# Meios_pagamento.net
KiCad netlist of a schematic drawn in Altium Designer
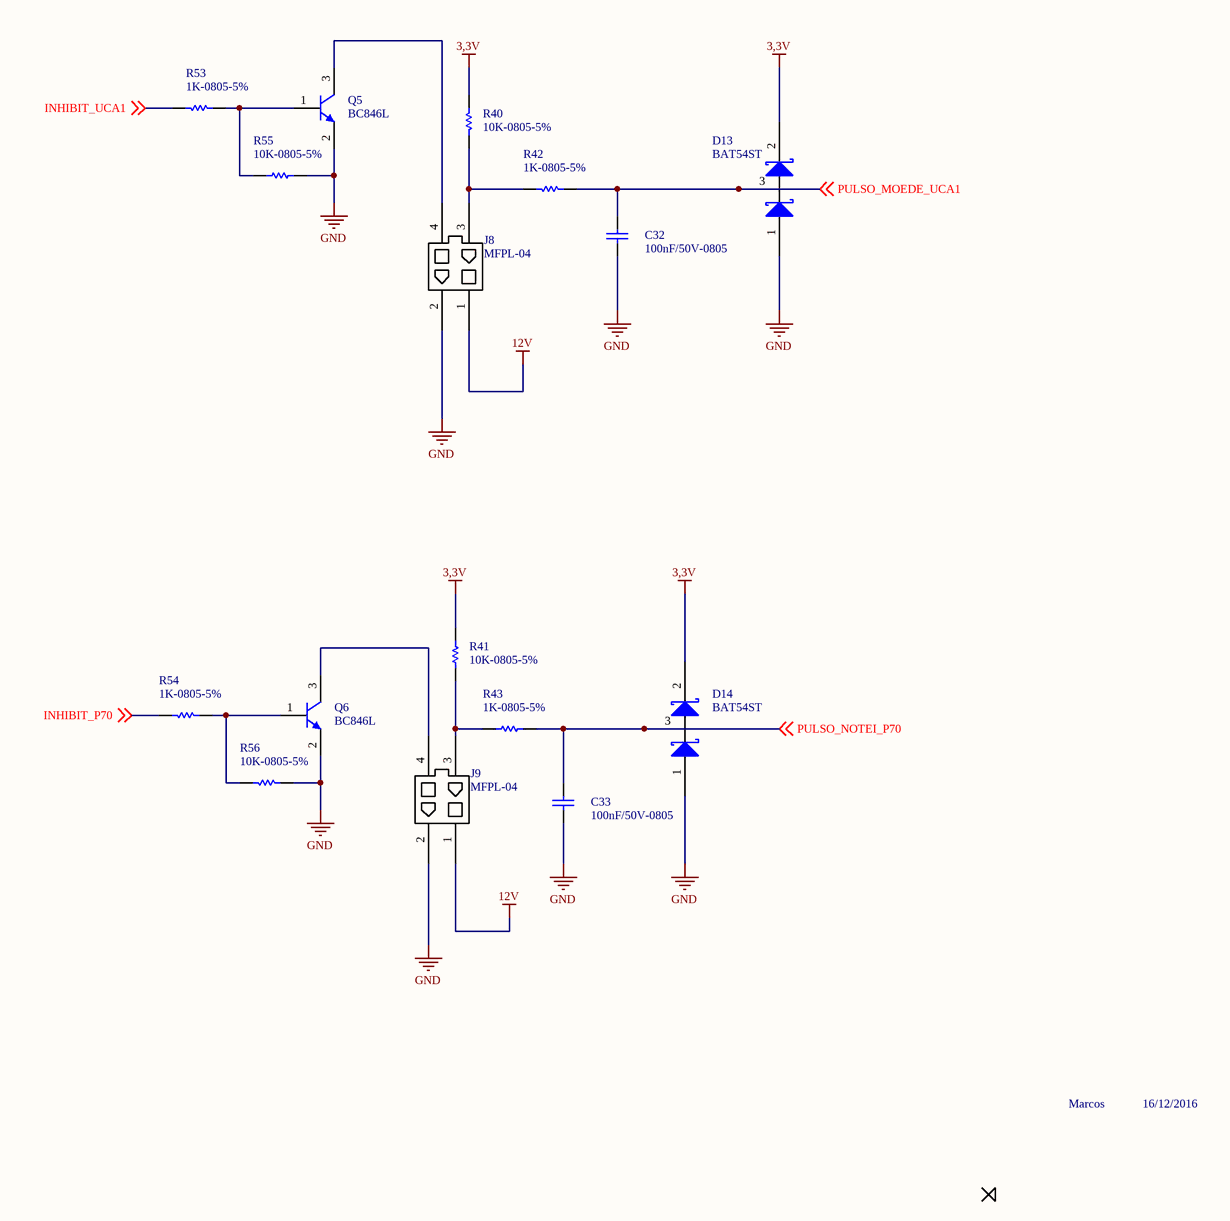
[diagram p0: Meios_pagamento.SchDoc]

(export (version "E")
  (design (tool "Eeschema 10.0.6"))
  (components
    (comp (ref "C32")
      (value "100nF/50V-0805")
      (footprint "0805-REVISADO ONDA")
      (libsource (lib "AquinoLib") (part "100nF/50-0805-NPO"))
    )
    (comp (ref "C33")
      (value "100nF/50V-0805")
      (footprint "0805-REVISADO ONDA")
      (libsource (lib "AquinoLib") (part "100nF/50-0805-NPO"))
    )
    (comp (ref "D13")
      (value "BAT54ST")
      (footprint "SOT23 - REVISADO ONDA")
      (libsource (lib "AquinoLib") (part "BAT54ST"))
    )
    (comp (ref "D14")
      (value "BAT54ST")
      (footprint "SOT23 - REVISADO ONDA")
      (libsource (lib "AquinoLib") (part "BAT54ST"))
    )
    (comp (ref "J8") (value "MFPL-04") (libsource (lib "AquinoLib") (part "MFPL-04")))
    (comp (ref "J9") (value "MFPL-04") (libsource (lib "AquinoLib") (part "MFPL-04")))
    (comp (ref "Q5")
      (value "BC846L")
      (footprint "SOT23 - REVISADO ONDA")
      (libsource (lib "AquinoLib") (part "BC846"))
    )
    (comp (ref "Q6")
      (value "BC846L")
      (footprint "SOT23 - REVISADO ONDA")
      (libsource (lib "AquinoLib") (part "BC846"))
    )
    (comp (ref "R40")
      (value "10K-0805-5%")
      (footprint "0805-REVISADO ONDA")
      (libsource (lib "AquinoLib") (part "10K-0805-5%"))
    )
    (comp (ref "R41")
      (value "10K-0805-5%")
      (footprint "0805-REVISADO ONDA")
      (libsource (lib "AquinoLib") (part "10K-0805-5%"))
    )
    (comp (ref "R42")
      (value "1K-0805-5%")
      (footprint "0805-REVISADO ONDA")
      (libsource (lib "AquinoLib") (part "1K-0805-5%"))
    )
    (comp (ref "R43")
      (value "1K-0805-5%")
      (footprint "0805-REVISADO ONDA")
      (libsource (lib "AquinoLib") (part "1K-0805-5%"))
    )
    (comp (ref "R53")
      (value "1K-0805-5%")
      (footprint "0805-REVISADO ONDA")
      (libsource (lib "AquinoLib") (part "1K-0805-5%"))
    )
    (comp (ref "R54")
      (value "1K-0805-5%")
      (footprint "0805-REVISADO ONDA")
      (libsource (lib "AquinoLib") (part "1K-0805-5%"))
    )
    (comp (ref "R55")
      (value "10K-0805-5%")
      (footprint "0805-REVISADO ONDA")
      (libsource (lib "AquinoLib") (part "10K-0805-5%"))
    )
    (comp (ref "R56")
      (value "10K-0805-5%")
      (footprint "0805-REVISADO ONDA")
      (libsource (lib "AquinoLib") (part "10K-0805-5%"))
    )
  )
  (nets
    (net (code "1") (name "3,3V") (class "Default")
      (node (ref "D13") (pin "2") (pinfunction "2_2") (pintype "passive"))
      (node (ref "D14") (pin "2") (pinfunction "2_2") (pintype "passive"))
      (node (ref "R40") (pin "2") (pinfunction "2_2") (pintype "passive"))
      (node (ref "R41") (pin "2") (pinfunction "2_2") (pintype "passive"))
    )
    (net (code "2") (name "12V") (class "Default")
      (node (ref "J8") (pin "1") (pinfunction "1_1") (pintype "passive"))
      (node (ref "J9") (pin "1") (pinfunction "1_1") (pintype "passive"))
    )
    (net (code "3") (name "GND") (class "Default")
      (node (ref "C32") (pin "1") (pinfunction "1_1") (pintype "passive"))
      (node (ref "C33") (pin "1") (pinfunction "1_1") (pintype "passive"))
      (node (ref "D13") (pin "1") (pinfunction "1_1") (pintype "passive"))
      (node (ref "D14") (pin "1") (pinfunction "1_1") (pintype "passive"))
      (node (ref "J8") (pin "2") (pinfunction "2_2") (pintype "passive"))
      (node (ref "J9") (pin "2") (pinfunction "2_2") (pintype "passive"))
      (node (ref "Q5") (pin "2") (pinfunction "E_2") (pintype "passive"))
      (node (ref "Q6") (pin "2") (pinfunction "E_2") (pintype "passive"))
      (node (ref "R55") (pin "2") (pinfunction "2_2") (pintype "passive"))
      (node (ref "R56") (pin "1") (pinfunction "1_1") (pintype "passive"))
    )
    (net (code "4") (name "INHIBIT_P70") (class "Default")
      (node (ref "R54") (pin "2") (pinfunction "2_2") (pintype "passive"))
    )
    (net (code "5") (name "INHIBIT_UCA1") (class "Default")
      (node (ref "R53") (pin "2") (pinfunction "2_2") (pintype "passive"))
    )
    (net (code "6") (name "Net-(J8-Pad3)") (class "Default")
      (node (ref "J8") (pin "3") (pinfunction "3_3") (pintype "passive"))
      (node (ref "R40") (pin "1") (pinfunction "1_1") (pintype "passive"))
      (node (ref "R42") (pin "2") (pinfunction "2_2") (pintype "passive"))
    )
    (net (code "7") (name "Net-(J9-Pad3)") (class "Default")
      (node (ref "J9") (pin "3") (pinfunction "3_3") (pintype "passive"))
      (node (ref "R41") (pin "1") (pinfunction "1_1") (pintype "passive"))
      (node (ref "R43") (pin "1") (pinfunction "1_1") (pintype "passive"))
    )
    (net (code "8") (name "Net-(Q5-B)") (class "Default")
      (node (ref "Q5") (pin "1") (pinfunction "B_1") (pintype "passive"))
      (node (ref "R53") (pin "1") (pinfunction "1_1") (pintype "passive"))
      (node (ref "R55") (pin "1") (pinfunction "1_1") (pintype "passive"))
    )
    (net (code "9") (name "Net-(Q5-C)") (class "Default")
      (node (ref "J8") (pin "4") (pinfunction "4_4") (pintype "passive"))
      (node (ref "Q5") (pin "3") (pinfunction "C_3") (pintype "passive"))
    )
    (net (code "10") (name "Net-(Q6-B)") (class "Default")
      (node (ref "Q6") (pin "1") (pinfunction "B_1") (pintype "passive"))
      (node (ref "R54") (pin "1") (pinfunction "1_1") (pintype "passive"))
      (node (ref "R56") (pin "2") (pinfunction "2_2") (pintype "passive"))
    )
    (net (code "11") (name "Net-(Q6-C)") (class "Default")
      (node (ref "J9") (pin "4") (pinfunction "4_4") (pintype "passive"))
      (node (ref "Q6") (pin "3") (pinfunction "C_3") (pintype "passive"))
    )
    (net (code "12") (name "PULSO_MOEDE_UCA1") (class "Default")
      (node (ref "C32") (pin "2") (pinfunction "2_2") (pintype "passive"))
      (node (ref "D13") (pin "3") (pinfunction "3_3") (pintype "passive"))
      (node (ref "R42") (pin "1") (pinfunction "1_1") (pintype "passive"))
    )
    (net (code "13") (name "PULSO_NOTEI_P70") (class "Default")
      (node (ref "C33") (pin "2") (pinfunction "2_2") (pintype "passive"))
      (node (ref "D14") (pin "3") (pinfunction "3_3") (pintype "passive"))
      (node (ref "R43") (pin "2") (pinfunction "2_2") (pintype "passive"))
    )
  )
)
